# 2_RS485_RS422.net
KiCad netlist of a schematic drawn in EAGLE
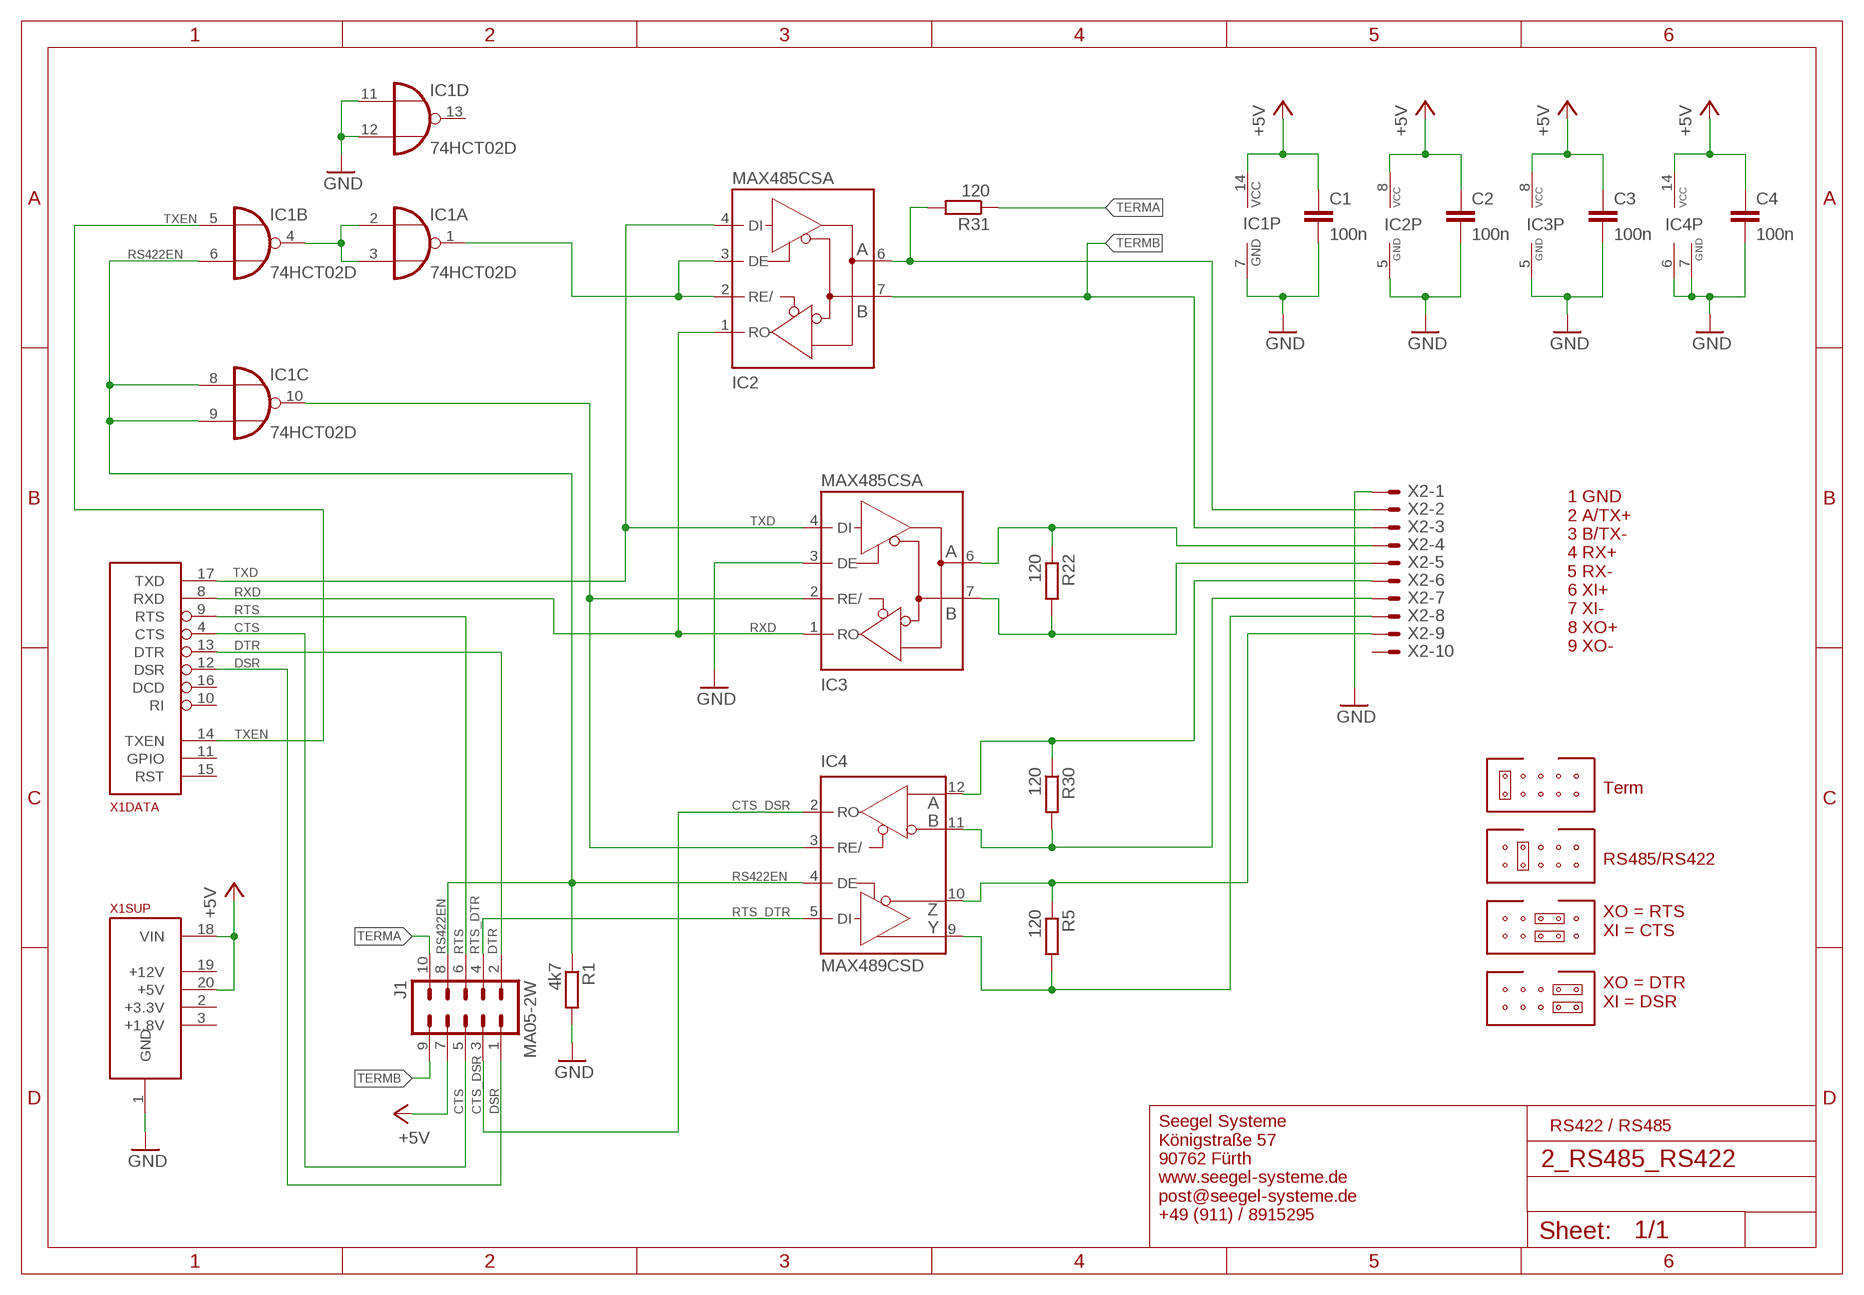
[diagram p0: schematic, sheet 1]

(export (version "E")
  (design (tool "Eeschema 10.0.6"))
  (components
    (comp (ref "C1")
      (value "100n")
      (footprint "eagle-import:C0805")
      (libsource (lib "eagle-import") (part "C-EUC0805"))
    )
    (comp (ref "C2")
      (value "100n")
      (footprint "eagle-import:C0805")
      (libsource (lib "eagle-import") (part "C-EUC0805"))
    )
    (comp (ref "C3")
      (value "100n")
      (footprint "eagle-import:C0805")
      (libsource (lib "eagle-import") (part "C-EUC0805"))
    )
    (comp (ref "C4")
      (value "100n")
      (footprint "eagle-import:C0805")
      (libsource (lib "eagle-import") (part "C-EUC0805"))
    )
    (comp (ref "IC1")
      (value "74HCT02D")
      (footprint "eagle-import:SO14")
      (libsource (lib "eagle-import") (part "7402DHCT"))
    )
    (comp (ref "IC2")
      (value "MAX485CSA")
      (footprint "eagle-import:SO08")
      (fields (field (name "MF") "MAXIM") (field (name "MPN") "MAX481CSA"))
      (libsource (lib "eagle-import") (part "MAX481CSA"))
    )
    (comp (ref "IC3")
      (value "MAX485CSA")
      (footprint "eagle-import:SO08")
      (fields (field (name "MF") "MAXIM") (field (name "MPN") "MAX481CSA"))
      (libsource (lib "eagle-import") (part "MAX481CSA"))
    )
    (comp (ref "IC4")
      (value "MAX489CSD")
      (footprint "eagle-import:SO14")
      (fields (field (name "MF") "MAXIM"))
      (libsource (lib "eagle-import") (part "MAX489CSD"))
    )
    (comp (ref "J1")
      (value "MA05-2W")
      (footprint "eagle-import:MA05-2W")
      (libsource (lib "eagle-import") (part "MA05-2W"))
    )
    (comp (ref "R1")
      (value "4k7")
      (footprint "eagle-import:R0805")
      (libsource (lib "eagle-import") (part "R-EU_R0805"))
    )
    (comp (ref "R5")
      (value "120")
      (footprint "eagle-import:R0805")
      (libsource (lib "eagle-import") (part "R-EU_R0805"))
    )
    (comp (ref "R22")
      (value "120")
      (footprint "eagle-import:R0805")
      (libsource (lib "eagle-import") (part "R-EU_R0805"))
    )
    (comp (ref "R30")
      (value "120")
      (footprint "eagle-import:R0805")
      (libsource (lib "eagle-import") (part "R-EU_R0805"))
    )
    (comp (ref "R31")
      (value "120")
      (footprint "eagle-import:R0805")
      (libsource (lib "eagle-import") (part "R-EU_R0805"))
    )
    (comp (ref "X1")
      (value "ALLSERIALSLAVE")
      (footprint "eagle-import:DAUGHTER-THT")
      (libsource (lib "eagle-import") (part "ALLSERIALSLAVE"))
    )
    (comp (ref "X2")
      (value "AKL18X-10W")
      (footprint "eagle-import:AKL182-10")
      (libsource (lib "eagle-import") (part "AKL18X-10W"))
    )
  )
  (nets
    (net (code "1") (name "+5V") (class "Default")
      (node (ref "C1") (pin "1") (pinfunction "1_1") (pintype "passive"))
      (node (ref "C2") (pin "1") (pinfunction "1_1") (pintype "passive"))
      (node (ref "C3") (pin "1") (pinfunction "1_1") (pintype "passive"))
      (node (ref "C4") (pin "1") (pinfunction "1_1") (pintype "passive"))
      (node (ref "IC1") (pin "14") (pinfunction "VCC_14") (pintype "power_in"))
      (node (ref "IC2") (pin "8") (pinfunction "VCC_8") (pintype "power_in"))
      (node (ref "IC3") (pin "8") (pinfunction "VCC_8") (pintype "power_in"))
      (node (ref "IC4") (pin "14") (pinfunction "VCC_14") (pintype "power_in"))
      (node (ref "J1") (pin "7") (pinfunction "7_7") (pintype "passive"))
      (node (ref "X1") (pin "18") (pinfunction "VIN_18") (pintype "bidirectional"))
      (node (ref "X1") (pin "20") (pinfunction "+5V_20") (pintype "bidirectional"))
    )
    (net (code "2") (name "/CTS") (class "Default")
      (node (ref "J1") (pin "5") (pinfunction "5_5") (pintype "passive"))
      (node (ref "X1") (pin "4") (pinfunction "CTS_4") (pintype "input"))
    )
    (net (code "3") (name "/CTS_DSR") (class "Default")
      (node (ref "IC4") (pin "2") (pinfunction "RO_2") (pintype "output"))
      (node (ref "J1") (pin "3") (pinfunction "3_3") (pintype "passive"))
    )
    (net (code "4") (name "/DSR") (class "Default")
      (node (ref "J1") (pin "1") (pinfunction "1_1") (pintype "passive"))
      (node (ref "X1") (pin "12") (pinfunction "DSR_12") (pintype "input"))
    )
    (net (code "5") (name "/DTR") (class "Default")
      (node (ref "J1") (pin "2") (pinfunction "2_2") (pintype "passive"))
      (node (ref "X1") (pin "13") (pinfunction "DTR_13") (pintype "output"))
    )
    (net (code "6") (name "/RS422EN") (class "Default")
      (node (ref "IC1") (pin "6") (pinfunction "I1_6") (pintype "input"))
      (node (ref "IC1") (pin "8") (pinfunction "I0_8") (pintype "input"))
      (node (ref "IC1") (pin "9") (pinfunction "I1_9") (pintype "input"))
      (node (ref "IC4") (pin "4") (pinfunction "DE_4") (pintype "input"))
      (node (ref "J1") (pin "8") (pinfunction "8_8") (pintype "passive"))
      (node (ref "R1") (pin "1") (pinfunction "1_1") (pintype "passive"))
    )
    (net (code "7") (name "/RTS") (class "Default")
      (node (ref "J1") (pin "6") (pinfunction "6_6") (pintype "passive"))
      (node (ref "X1") (pin "9") (pinfunction "RTS_9") (pintype "output"))
    )
    (net (code "8") (name "/RTS_DTR") (class "Default")
      (node (ref "IC4") (pin "5") (pinfunction "DI_5") (pintype "input"))
      (node (ref "J1") (pin "4") (pinfunction "4_4") (pintype "passive"))
    )
    (net (code "9") (name "/RXD") (class "Default")
      (node (ref "IC2") (pin "1") (pinfunction "RO_1") (pintype "output"))
      (node (ref "IC3") (pin "1") (pinfunction "RO_1") (pintype "output"))
      (node (ref "X1") (pin "8") (pinfunction "RXD_8") (pintype "input"))
    )
    (net (code "10") (name "/TXD") (class "Default")
      (node (ref "IC2") (pin "4") (pinfunction "DI_4") (pintype "input"))
      (node (ref "IC3") (pin "4") (pinfunction "DI_4") (pintype "input"))
      (node (ref "X1") (pin "17") (pinfunction "TXD_17") (pintype "output"))
    )
    (net (code "11") (name "/TXEN") (class "Default")
      (node (ref "IC1") (pin "5") (pinfunction "I0_5") (pintype "input"))
      (node (ref "X1") (pin "14") (pinfunction "TXEN_14") (pintype "output"))
    )
    (net (code "12") (name "GND") (class "Default")
      (node (ref "C1") (pin "2") (pinfunction "2_2") (pintype "passive"))
      (node (ref "C2") (pin "2") (pinfunction "2_2") (pintype "passive"))
      (node (ref "C3") (pin "2") (pinfunction "2_2") (pintype "passive"))
      (node (ref "C4") (pin "2") (pinfunction "2_2") (pintype "passive"))
      (node (ref "IC1") (pin "11") (pinfunction "I0_11") (pintype "input"))
      (node (ref "IC1") (pin "12") (pinfunction "I1_12") (pintype "input"))
      (node (ref "IC1") (pin "7") (pinfunction "GND_7") (pintype "power_in"))
      (node (ref "IC2") (pin "5") (pinfunction "GND_5") (pintype "power_in"))
      (node (ref "IC3") (pin "3") (pinfunction "DE_3") (pintype "input"))
      (node (ref "IC3") (pin "5") (pinfunction "GND_5") (pintype "power_in"))
      (node (ref "IC4") (pin "6") (pinfunction "GND_6") (pintype "power_in"))
      (node (ref "IC4") (pin "7") (pinfunction "GND_7") (pintype "power_in"))
      (node (ref "R1") (pin "2") (pinfunction "2_2") (pintype "passive"))
      (node (ref "X1") (pin "1") (pinfunction "GND_1") (pintype "bidirectional"))
      (node (ref "X2") (pin "P$1") (pinfunction "S_P$1") (pintype "passive"))
    )
    (net (code "13") (name "Net-(IC1A-I0)") (class "Default")
      (node (ref "IC1") (pin "2") (pinfunction "I0_2") (pintype "input"))
      (node (ref "IC1") (pin "3") (pinfunction "I1_3") (pintype "input"))
      (node (ref "IC1") (pin "4") (pinfunction "O_4") (pintype "output"))
    )
    (net (code "14") (name "Net-(IC1A-O)") (class "Default")
      (node (ref "IC1") (pin "1") (pinfunction "O_1") (pintype "output"))
      (node (ref "IC2") (pin "2") (pinfunction "RE/_2") (pintype "input"))
      (node (ref "IC2") (pin "3") (pinfunction "DE_3") (pintype "input"))
    )
    (net (code "15") (name "Net-(IC1C-O)") (class "Default")
      (node (ref "IC1") (pin "10") (pinfunction "O_10") (pintype "output"))
      (node (ref "IC3") (pin "2") (pinfunction "RE/_2") (pintype "input"))
      (node (ref "IC4") (pin "3") (pinfunction "RE/_3") (pintype "input"))
    )
    (net (code "16") (name "Net-(IC2A-A)") (class "Default")
      (node (ref "IC2") (pin "6") (pinfunction "A_6") (pintype "passive"))
      (node (ref "R31") (pin "2") (pinfunction "2_2") (pintype "passive"))
      (node (ref "X2") (pin "P$2") (pinfunction "S_P$2") (pintype "passive"))
    )
    (net (code "17") (name "Net-(IC3A-A)") (class "Default")
      (node (ref "IC3") (pin "6") (pinfunction "A_6") (pintype "passive"))
      (node (ref "R22") (pin "1") (pinfunction "1_1") (pintype "passive"))
      (node (ref "X2") (pin "P$4") (pinfunction "S_P$4") (pintype "passive"))
    )
    (net (code "18") (name "Net-(IC3A-B)") (class "Default")
      (node (ref "IC3") (pin "7") (pinfunction "B_7") (pintype "passive"))
      (node (ref "R22") (pin "2") (pinfunction "2_2") (pintype "passive"))
      (node (ref "X2") (pin "P$5") (pinfunction "S_P$5") (pintype "passive"))
    )
    (net (code "19") (name "Net-(IC4D-A)") (class "Default")
      (node (ref "IC4") (pin "12") (pinfunction "A_12") (pintype "passive"))
      (node (ref "R30") (pin "1") (pinfunction "1_1") (pintype "passive"))
      (node (ref "X2") (pin "P$6") (pinfunction "S_P$6") (pintype "passive"))
    )
    (net (code "20") (name "Net-(IC4D-B)") (class "Default")
      (node (ref "IC4") (pin "11") (pinfunction "B_11") (pintype "passive"))
      (node (ref "R30") (pin "2") (pinfunction "2_2") (pintype "passive"))
      (node (ref "X2") (pin "P$7") (pinfunction "S_P$7") (pintype "passive"))
    )
    (net (code "21") (name "Net-(IC4D-Y)") (class "Default")
      (node (ref "IC4") (pin "9") (pinfunction "Y_9") (pintype "passive"))
      (node (ref "R5") (pin "2") (pinfunction "2_2") (pintype "passive"))
      (node (ref "X2") (pin "P$8") (pinfunction "S_P$8") (pintype "passive"))
    )
    (net (code "22") (name "Net-(IC4D-Z)") (class "Default")
      (node (ref "IC4") (pin "10") (pinfunction "Z_10") (pintype "passive"))
      (node (ref "R5") (pin "1") (pinfunction "1_1") (pintype "passive"))
      (node (ref "X2") (pin "P$9") (pinfunction "S_P$9") (pintype "passive"))
    )
    (net (code "23") (name "TERMA") (class "Default")
      (node (ref "J1") (pin "10") (pinfunction "10_10") (pintype "passive"))
      (node (ref "R31") (pin "1") (pinfunction "1_1") (pintype "passive"))
    )
    (net (code "24") (name "TERMB") (class "Default")
      (node (ref "IC2") (pin "7") (pinfunction "B_7") (pintype "passive"))
      (node (ref "J1") (pin "9") (pinfunction "9_9") (pintype "passive"))
      (node (ref "X2") (pin "P$3") (pinfunction "S_P$3") (pintype "passive"))
    )
    (net (code "25") (name "unconnected-(IC1D-O-Pad13)") (class "Default")
      (node (ref "IC1") (pin "13") (pinfunction "O_13") (pintype "output"))
    )
    (net (code "26") (name "unconnected-(X1A-DCD-Pad16)") (class "Default")
      (node (ref "X1") (pin "16") (pinfunction "DCD_16") (pintype "input"))
    )
    (net (code "27") (name "unconnected-(X1A-GPIO-Pad11)") (class "Default")
      (node (ref "X1") (pin "11") (pinfunction "GPIO_11") (pintype "bidirectional"))
    )
    (net (code "28") (name "unconnected-(X1A-RI-Pad10)") (class "Default")
      (node (ref "X1") (pin "10") (pinfunction "RI_10") (pintype "input"))
    )
    (net (code "29") (name "unconnected-(X1A-RST-Pad15)") (class "Default")
      (node (ref "X1") (pin "15") (pinfunction "RST_15") (pintype "bidirectional"))
    )
    (net (code "30") (name "unconnected-(X1B-+1.8V-Pad3)") (class "Default")
      (node (ref "X1") (pin "3") (pinfunction "+1.8V_3") (pintype "bidirectional"))
    )
    (net (code "31") (name "unconnected-(X1B-+3.3V-Pad2)") (class "Default")
      (node (ref "X1") (pin "2") (pinfunction "+3.3V_2") (pintype "bidirectional"))
    )
    (net (code "32") (name "unconnected-(X1B-+12V-Pad19)") (class "Default")
      (node (ref "X1") (pin "19") (pinfunction "+12V_19") (pintype "bidirectional"))
    )
    (net (code "33") (name "unconnected-(X2B-S-PadP$10)") (class "Default")
      (node (ref "X2") (pin "P$10") (pinfunction "S_P$10") (pintype "passive"))
    )
  )
)
